# remote.net
KiCad netlist of a schematic drawn in EAGLE
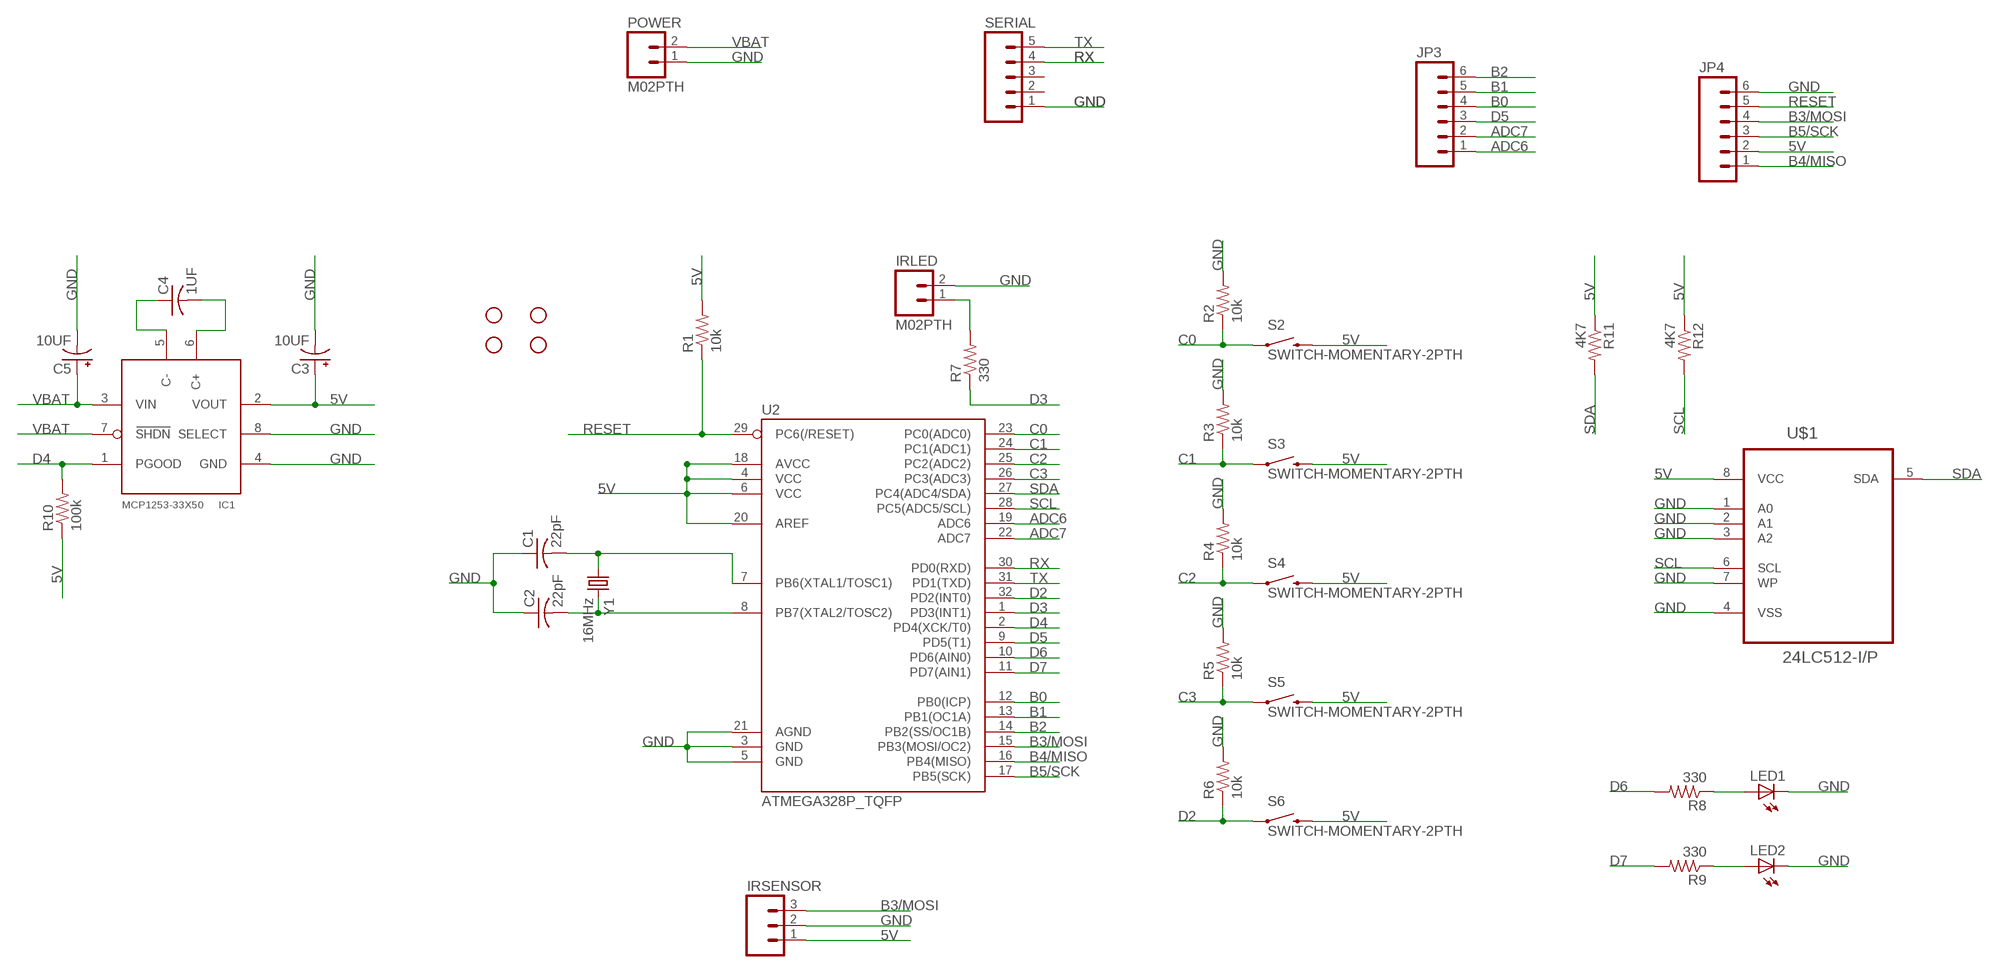
[diagram p0: schematic, sheet 1]

(export (version "E")
  (design (tool "Eeschema 10.0.6"))
  (components
    (comp (ref "C1")
      (value "22pF")
      (footprint "eagle-import:C0805")
      (libsource (lib "eagle-import") (part "C-USC0805"))
    )
    (comp (ref "C2")
      (value "22pF")
      (footprint "eagle-import:C0805")
      (libsource (lib "eagle-import") (part "C-USC0805"))
    )
    (comp (ref "C3")
      (value "10UF")
      (footprint "eagle-import:A_3216-18W")
      (libsource (lib "eagle-import") (part "CPOL-USA/3216-18W"))
    )
    (comp (ref "C4")
      (value "1UF")
      (footprint "eagle-import:C0805")
      (libsource (lib "eagle-import") (part "C-USC0805"))
    )
    (comp (ref "C5")
      (value "10UF")
      (footprint "eagle-import:A_3216-18W")
      (libsource (lib "eagle-import") (part "CPOL-USA/3216-18W"))
    )
    (comp (ref "IC1")
      (value "MCP1253-33X50")
      (footprint "eagle-import:MSOP8")
      (libsource (lib "eagle-import") (part "MCP1253-33X50"))
    )
    (comp (ref "IRLED")
      (value "M02PTH")
      (footprint "eagle-import:1X02")
      (libsource (lib "eagle-import") (part "M02PTH"))
    )
    (comp (ref "IRSENSOR")
      (value "M03PTH")
      (footprint "eagle-import:1X03")
      (libsource (lib "eagle-import") (part "M03PTH"))
    )
    (comp (ref "JP1")
      (value "STAND-OFF")
      (footprint "eagle-import:STAND-OFF")
      (libsource (lib "eagle-import") (part "STAND-OFF"))
    )
    (comp (ref "JP2")
      (value "STAND-OFF")
      (footprint "eagle-import:STAND-OFF")
      (libsource (lib "eagle-import") (part "STAND-OFF"))
    )
    (comp (ref "JP3")
      (value "M06SIP")
      (footprint "eagle-import:1X06")
      (libsource (lib "eagle-import") (part "M06SIP"))
    )
    (comp (ref "JP4")
      (value "M06SIP")
      (footprint "eagle-import:1X06")
      (libsource (lib "eagle-import") (part "M06SIP"))
    )
    (comp (ref "JP6")
      (value "STAND-OFF")
      (footprint "eagle-import:STAND-OFF")
      (libsource (lib "eagle-import") (part "STAND-OFF"))
    )
    (comp (ref "JP7")
      (value "STAND-OFF")
      (footprint "eagle-import:STAND-OFF")
      (libsource (lib "eagle-import") (part "STAND-OFF"))
    )
    (comp (ref "LED1")
      (value "LEDCHIPLED_0805")
      (footprint "eagle-import:CHIPLED_0805")
      (libsource (lib "eagle-import") (part "LEDCHIPLED_0805"))
    )
    (comp (ref "LED2")
      (value "LEDCHIPLED_0805")
      (footprint "eagle-import:CHIPLED_0805")
      (libsource (lib "eagle-import") (part "LEDCHIPLED_0805"))
    )
    (comp (ref "POWER")
      (value "M02PTH")
      (footprint "eagle-import:1X02")
      (libsource (lib "eagle-import") (part "M02PTH"))
    )
    (comp (ref "R1")
      (value "10k")
      (footprint "eagle-import:R0805")
      (libsource (lib "eagle-import") (part "R-US_R0805"))
    )
    (comp (ref "R2")
      (value "10k")
      (footprint "eagle-import:R0805")
      (libsource (lib "eagle-import") (part "R-US_R0805"))
    )
    (comp (ref "R3")
      (value "10k")
      (footprint "eagle-import:R0805")
      (libsource (lib "eagle-import") (part "R-US_R0805"))
    )
    (comp (ref "R4")
      (value "10k")
      (footprint "eagle-import:R0805")
      (libsource (lib "eagle-import") (part "R-US_R0805"))
    )
    (comp (ref "R5")
      (value "10k")
      (footprint "eagle-import:R0805")
      (libsource (lib "eagle-import") (part "R-US_R0805"))
    )
    (comp (ref "R6")
      (value "10k")
      (footprint "eagle-import:R0805")
      (libsource (lib "eagle-import") (part "R-US_R0805"))
    )
    (comp (ref "R7")
      (value "330")
      (footprint "eagle-import:R0805")
      (libsource (lib "eagle-import") (part "R-US_R0805"))
    )
    (comp (ref "R8")
      (value "330")
      (footprint "eagle-import:R0805")
      (libsource (lib "eagle-import") (part "R-US_R0805"))
    )
    (comp (ref "R9")
      (value "330")
      (footprint "eagle-import:R0805")
      (libsource (lib "eagle-import") (part "R-US_R0805"))
    )
    (comp (ref "R10")
      (value "100k")
      (footprint "eagle-import:R0805")
      (libsource (lib "eagle-import") (part "R-US_R0805"))
    )
    (comp (ref "R11")
      (value "4K7")
      (footprint "eagle-import:R0805")
      (libsource (lib "eagle-import") (part "R-US_R0805"))
    )
    (comp (ref "R12")
      (value "4K7")
      (footprint "eagle-import:R0805")
      (libsource (lib "eagle-import") (part "R-US_R0805"))
    )
    (comp (ref "S2")
      (value "SWITCH-MOMENTARY-2PTH")
      (footprint "eagle-import:TACTILE-PTH")
      (libsource (lib "eagle-import") (part "SWITCH-MOMENTARY-2PTH"))
    )
    (comp (ref "S3")
      (value "SWITCH-MOMENTARY-2PTH")
      (footprint "eagle-import:TACTILE-PTH")
      (libsource (lib "eagle-import") (part "SWITCH-MOMENTARY-2PTH"))
    )
    (comp (ref "S4")
      (value "SWITCH-MOMENTARY-2PTH")
      (footprint "eagle-import:TACTILE-PTH")
      (libsource (lib "eagle-import") (part "SWITCH-MOMENTARY-2PTH"))
    )
    (comp (ref "S5")
      (value "SWITCH-MOMENTARY-2PTH")
      (footprint "eagle-import:TACTILE-PTH")
      (libsource (lib "eagle-import") (part "SWITCH-MOMENTARY-2PTH"))
    )
    (comp (ref "S6")
      (value "SWITCH-MOMENTARY-2PTH")
      (footprint "eagle-import:TACTILE-PTH")
      (libsource (lib "eagle-import") (part "SWITCH-MOMENTARY-2PTH"))
    )
    (comp (ref "SERIAL")
      (value "M05PTH")
      (footprint "eagle-import:1X05")
      (libsource (lib "eagle-import") (part "M05PTH"))
    )
    (comp (ref "U$1")
      (value "24LC512-I/P")
      (footprint "eagle-import:DIP254P762X432-8")
      (libsource (lib "eagle-import") (part "24LC512-I/P"))
    )
    (comp (ref "U2")
      (value "ATMEGA328P_TQFP")
      (footprint "eagle-import:TQFP32-08")
      (libsource (lib "eagle-import") (part "ATMEGA328P_TQFP"))
    )
    (comp (ref "Y1")
      (value "16MHz")
      (footprint "eagle-import:HC49US")
      (libsource (lib "eagle-import") (part "CRYSTALHC49US"))
    )
  )
  (nets
    (net (code "1") (name "/5V") (class "Default")
      (node (ref "C3") (pin "+") (pinfunction "+_+") (pintype "passive"))
      (node (ref "IC1") (pin "2") (pinfunction "VOUT_2") (pintype "output"))
      (node (ref "IRSENSOR") (pin "1") (pinfunction "1_1") (pintype "passive"))
      (node (ref "JP4") (pin "2") (pinfunction "2_2") (pintype "passive"))
      (node (ref "R1") (pin "2") (pinfunction "2_2") (pintype "passive"))
      (node (ref "R10") (pin "1") (pinfunction "1_1") (pintype "passive"))
      (node (ref "R11") (pin "1") (pinfunction "1_1") (pintype "passive"))
      (node (ref "R12") (pin "1") (pinfunction "1_1") (pintype "passive"))
      (node (ref "S2") (pin "3") (pinfunction "2_3") (pintype "passive"))
      (node (ref "S3") (pin "3") (pinfunction "2_3") (pintype "passive"))
      (node (ref "S4") (pin "3") (pinfunction "2_3") (pintype "passive"))
      (node (ref "S5") (pin "3") (pinfunction "2_3") (pintype "passive"))
      (node (ref "S6") (pin "3") (pinfunction "2_3") (pintype "passive"))
      (node (ref "U$1") (pin "8") (pinfunction "VCC_8") (pintype "power_in"))
      (node (ref "U2") (pin "18") (pinfunction "AVCC_18") (pintype "bidirectional"))
      (node (ref "U2") (pin "20") (pinfunction "AREF_20") (pintype "bidirectional"))
      (node (ref "U2") (pin "4") (pinfunction "VCC_4") (pintype "bidirectional"))
      (node (ref "U2") (pin "6") (pinfunction "VCC_6") (pintype "bidirectional"))
    )
    (net (code "2") (name "/ADC6") (class "Default")
      (node (ref "JP3") (pin "1") (pinfunction "1_1") (pintype "passive"))
      (node (ref "U2") (pin "19") (pinfunction "ADC6_19") (pintype "bidirectional"))
    )
    (net (code "3") (name "/ADC7") (class "Default")
      (node (ref "JP3") (pin "2") (pinfunction "2_2") (pintype "passive"))
      (node (ref "U2") (pin "22") (pinfunction "ADC7_22") (pintype "bidirectional"))
    )
    (net (code "4") (name "/B0") (class "Default")
      (node (ref "JP3") (pin "4") (pinfunction "4_4") (pintype "passive"))
      (node (ref "U2") (pin "12") (pinfunction "PB0(ICP)_12") (pintype "bidirectional"))
    )
    (net (code "5") (name "/B1") (class "Default")
      (node (ref "JP3") (pin "5") (pinfunction "5_5") (pintype "passive"))
      (node (ref "U2") (pin "13") (pinfunction "PB1(OC1A)_13") (pintype "bidirectional"))
    )
    (net (code "6") (name "/B2") (class "Default")
      (node (ref "JP3") (pin "6") (pinfunction "6_6") (pintype "passive"))
      (node (ref "U2") (pin "14") (pinfunction "PB2(SS/OC1B)_14") (pintype "bidirectional"))
    )
    (net (code "7") (name "/B3{slash}MOSI") (class "Default")
      (node (ref "IRSENSOR") (pin "3") (pinfunction "3_3") (pintype "passive"))
      (node (ref "JP4") (pin "4") (pinfunction "4_4") (pintype "passive"))
      (node (ref "U2") (pin "15") (pinfunction "PB3(MOSI/OC2)_15") (pintype "bidirectional"))
    )
    (net (code "8") (name "/B4{slash}MISO") (class "Default")
      (node (ref "JP4") (pin "1") (pinfunction "1_1") (pintype "passive"))
      (node (ref "U2") (pin "16") (pinfunction "PB4(MISO)_16") (pintype "bidirectional"))
    )
    (net (code "9") (name "/B5{slash}SCK") (class "Default")
      (node (ref "JP4") (pin "3") (pinfunction "3_3") (pintype "passive"))
      (node (ref "U2") (pin "17") (pinfunction "PB5(SCK)_17") (pintype "bidirectional"))
    )
    (net (code "10") (name "/C0") (class "Default")
      (node (ref "R2") (pin "1") (pinfunction "1_1") (pintype "passive"))
      (node (ref "S2") (pin "1") (pinfunction "1_1") (pintype "passive"))
      (node (ref "U2") (pin "23") (pinfunction "PC0(ADC0)_23") (pintype "bidirectional"))
    )
    (net (code "11") (name "/C1") (class "Default")
      (node (ref "R3") (pin "1") (pinfunction "1_1") (pintype "passive"))
      (node (ref "S3") (pin "1") (pinfunction "1_1") (pintype "passive"))
      (node (ref "U2") (pin "24") (pinfunction "PC1(ADC1)_24") (pintype "bidirectional"))
    )
    (net (code "12") (name "/C2") (class "Default")
      (node (ref "R4") (pin "1") (pinfunction "1_1") (pintype "passive"))
      (node (ref "S4") (pin "1") (pinfunction "1_1") (pintype "passive"))
      (node (ref "U2") (pin "25") (pinfunction "PC2(ADC2)_25") (pintype "bidirectional"))
    )
    (net (code "13") (name "/C3") (class "Default")
      (node (ref "R5") (pin "1") (pinfunction "1_1") (pintype "passive"))
      (node (ref "S5") (pin "1") (pinfunction "1_1") (pintype "passive"))
      (node (ref "U2") (pin "26") (pinfunction "PC3(ADC3)_26") (pintype "bidirectional"))
    )
    (net (code "14") (name "/D2") (class "Default")
      (node (ref "R6") (pin "1") (pinfunction "1_1") (pintype "passive"))
      (node (ref "S6") (pin "1") (pinfunction "1_1") (pintype "passive"))
      (node (ref "U2") (pin "32") (pinfunction "PD2(INT0)_32") (pintype "bidirectional"))
    )
    (net (code "15") (name "/D3") (class "Default")
      (node (ref "R7") (pin "1") (pinfunction "1_1") (pintype "passive"))
      (node (ref "U2") (pin "1") (pinfunction "PD3(INT1)_1") (pintype "bidirectional"))
    )
    (net (code "16") (name "/D4") (class "Default")
      (node (ref "IC1") (pin "1") (pinfunction "PGOOD_1") (pintype "output"))
      (node (ref "R10") (pin "2") (pinfunction "2_2") (pintype "passive"))
      (node (ref "U2") (pin "2") (pinfunction "PD4(XCK/T0)_2") (pintype "bidirectional"))
    )
    (net (code "17") (name "/D5") (class "Default")
      (node (ref "JP3") (pin "3") (pinfunction "3_3") (pintype "passive"))
      (node (ref "U2") (pin "9") (pinfunction "PD5(T1)_9") (pintype "bidirectional"))
    )
    (net (code "18") (name "/D6") (class "Default")
      (node (ref "R8") (pin "2") (pinfunction "2_2") (pintype "passive"))
      (node (ref "U2") (pin "10") (pinfunction "PD6(AIN0)_10") (pintype "bidirectional"))
    )
    (net (code "19") (name "/D7") (class "Default")
      (node (ref "R9") (pin "2") (pinfunction "2_2") (pintype "passive"))
      (node (ref "U2") (pin "11") (pinfunction "PD7(AIN1)_11") (pintype "bidirectional"))
    )
    (net (code "20") (name "/GND") (class "Default")
      (node (ref "C1") (pin "1") (pinfunction "1_1") (pintype "passive"))
      (node (ref "C2") (pin "1") (pinfunction "1_1") (pintype "passive"))
      (node (ref "C3") (pin "-") (pinfunction "-_-") (pintype "passive"))
      (node (ref "C5") (pin "-") (pinfunction "-_-") (pintype "passive"))
      (node (ref "IC1") (pin "4") (pinfunction "GND_4") (pintype "power_in"))
      (node (ref "IC1") (pin "8") (pinfunction "SELECT_8") (pintype "input"))
      (node (ref "IRLED") (pin "2") (pinfunction "2_2") (pintype "passive"))
      (node (ref "IRSENSOR") (pin "2") (pinfunction "2_2") (pintype "passive"))
      (node (ref "JP4") (pin "6") (pinfunction "6_6") (pintype "passive"))
      (node (ref "LED1") (pin "C") (pinfunction "C_C") (pintype "passive"))
      (node (ref "LED2") (pin "C") (pinfunction "C_C") (pintype "passive"))
      (node (ref "POWER") (pin "1") (pinfunction "1_1") (pintype "passive"))
      (node (ref "R2") (pin "2") (pinfunction "2_2") (pintype "passive"))
      (node (ref "R3") (pin "2") (pinfunction "2_2") (pintype "passive"))
      (node (ref "R4") (pin "2") (pinfunction "2_2") (pintype "passive"))
      (node (ref "R5") (pin "2") (pinfunction "2_2") (pintype "passive"))
      (node (ref "R6") (pin "2") (pinfunction "2_2") (pintype "passive"))
      (node (ref "SERIAL") (pin "1") (pinfunction "1_1") (pintype "passive"))
      (node (ref "U$1") (pin "1") (pinfunction "A0_1") (pintype "input"))
      (node (ref "U$1") (pin "2") (pinfunction "A1_2") (pintype "input"))
      (node (ref "U$1") (pin "3") (pinfunction "A2_3") (pintype "input"))
      (node (ref "U$1") (pin "4") (pinfunction "VSS_4") (pintype "passive"))
      (node (ref "U$1") (pin "7") (pinfunction "WP_7") (pintype "input"))
      (node (ref "U2") (pin "21") (pinfunction "AGND_21") (pintype "bidirectional"))
      (node (ref "U2") (pin "3") (pinfunction "GND_3") (pintype "bidirectional"))
      (node (ref "U2") (pin "5") (pinfunction "GND_5") (pintype "bidirectional"))
    )
    (net (code "21") (name "/RESET") (class "Default")
      (node (ref "JP4") (pin "5") (pinfunction "5_5") (pintype "passive"))
      (node (ref "R1") (pin "1") (pinfunction "1_1") (pintype "passive"))
      (node (ref "U2") (pin "29") (pinfunction "PC6(/RESET)_29") (pintype "bidirectional"))
    )
    (net (code "22") (name "/RX") (class "Default")
      (node (ref "SERIAL") (pin "4") (pinfunction "4_4") (pintype "passive"))
      (node (ref "U2") (pin "30") (pinfunction "PD0(RXD)_30") (pintype "bidirectional"))
    )
    (net (code "23") (name "/SCL") (class "Default")
      (node (ref "R12") (pin "2") (pinfunction "2_2") (pintype "passive"))
      (node (ref "U$1") (pin "6") (pinfunction "SCL_6") (pintype "input"))
      (node (ref "U2") (pin "28") (pinfunction "PC5(ADC5/SCL)_28") (pintype "bidirectional"))
    )
    (net (code "24") (name "/SDA") (class "Default")
      (node (ref "R11") (pin "2") (pinfunction "2_2") (pintype "passive"))
      (node (ref "U$1") (pin "5") (pinfunction "SDA_5") (pintype "bidirectional"))
      (node (ref "U2") (pin "27") (pinfunction "PC4(ADC4/SDA)_27") (pintype "bidirectional"))
    )
    (net (code "25") (name "/TX") (class "Default")
      (node (ref "SERIAL") (pin "5") (pinfunction "5_5") (pintype "passive"))
      (node (ref "U2") (pin "31") (pinfunction "PD1(TXD)_31") (pintype "bidirectional"))
    )
    (net (code "26") (name "/VBAT") (class "Default")
      (node (ref "C5") (pin "+") (pinfunction "+_+") (pintype "passive"))
      (node (ref "IC1") (pin "3") (pinfunction "VIN_3") (pintype "power_in"))
      (node (ref "IC1") (pin "7") (pinfunction "SHDN_7") (pintype "input"))
      (node (ref "POWER") (pin "2") (pinfunction "2_2") (pintype "passive"))
    )
    (net (code "27") (name "Net-(IC1-C+)") (class "Default")
      (node (ref "C4") (pin "2") (pinfunction "2_2") (pintype "passive"))
      (node (ref "IC1") (pin "6") (pinfunction "C+_6") (pintype "passive"))
    )
    (net (code "28") (name "Net-(IC1-C-)") (class "Default")
      (node (ref "C4") (pin "1") (pinfunction "1_1") (pintype "passive"))
      (node (ref "IC1") (pin "5") (pinfunction "C-_5") (pintype "passive"))
    )
    (net (code "29") (name "Net-(IRLED-Pad1)") (class "Default")
      (node (ref "IRLED") (pin "1") (pinfunction "1_1") (pintype "passive"))
      (node (ref "R7") (pin "2") (pinfunction "2_2") (pintype "passive"))
    )
    (net (code "30") (name "Net-(LED1-PadA)") (class "Default")
      (node (ref "LED1") (pin "A") (pinfunction "A_A") (pintype "passive"))
      (node (ref "R8") (pin "1") (pinfunction "1_1") (pintype "passive"))
    )
    (net (code "31") (name "Net-(LED2-PadA)") (class "Default")
      (node (ref "LED2") (pin "A") (pinfunction "A_A") (pintype "passive"))
      (node (ref "R9") (pin "1") (pinfunction "1_1") (pintype "passive"))
    )
    (net (code "32") (name "Net-(U2-PB6(XTAL1{slash}TOSC1))") (class "Default")
      (node (ref "C1") (pin "2") (pinfunction "2_2") (pintype "passive"))
      (node (ref "U2") (pin "7") (pinfunction "PB6(XTAL1/TOSC1)_7") (pintype "bidirectional"))
      (node (ref "Y1") (pin "1") (pinfunction "1_1") (pintype "passive"))
    )
    (net (code "33") (name "Net-(U2-PB7(XTAL2{slash}TOSC2))") (class "Default")
      (node (ref "C2") (pin "2") (pinfunction "2_2") (pintype "passive"))
      (node (ref "U2") (pin "8") (pinfunction "PB7(XTAL2/TOSC2)_8") (pintype "bidirectional"))
      (node (ref "Y1") (pin "2") (pinfunction "2_2") (pintype "passive"))
    )
    (net (code "34") (name "unconnected-(SERIAL-Pad2)") (class "Default")
      (node (ref "SERIAL") (pin "2") (pinfunction "2_2") (pintype "passive"))
    )
    (net (code "35") (name "unconnected-(SERIAL-Pad3)") (class "Default")
      (node (ref "SERIAL") (pin "3") (pinfunction "3_3") (pintype "passive"))
    )
  )
)
